# tiny_fox_predatronics.net
KiCad netlist of a schematic drawn in EAGLE
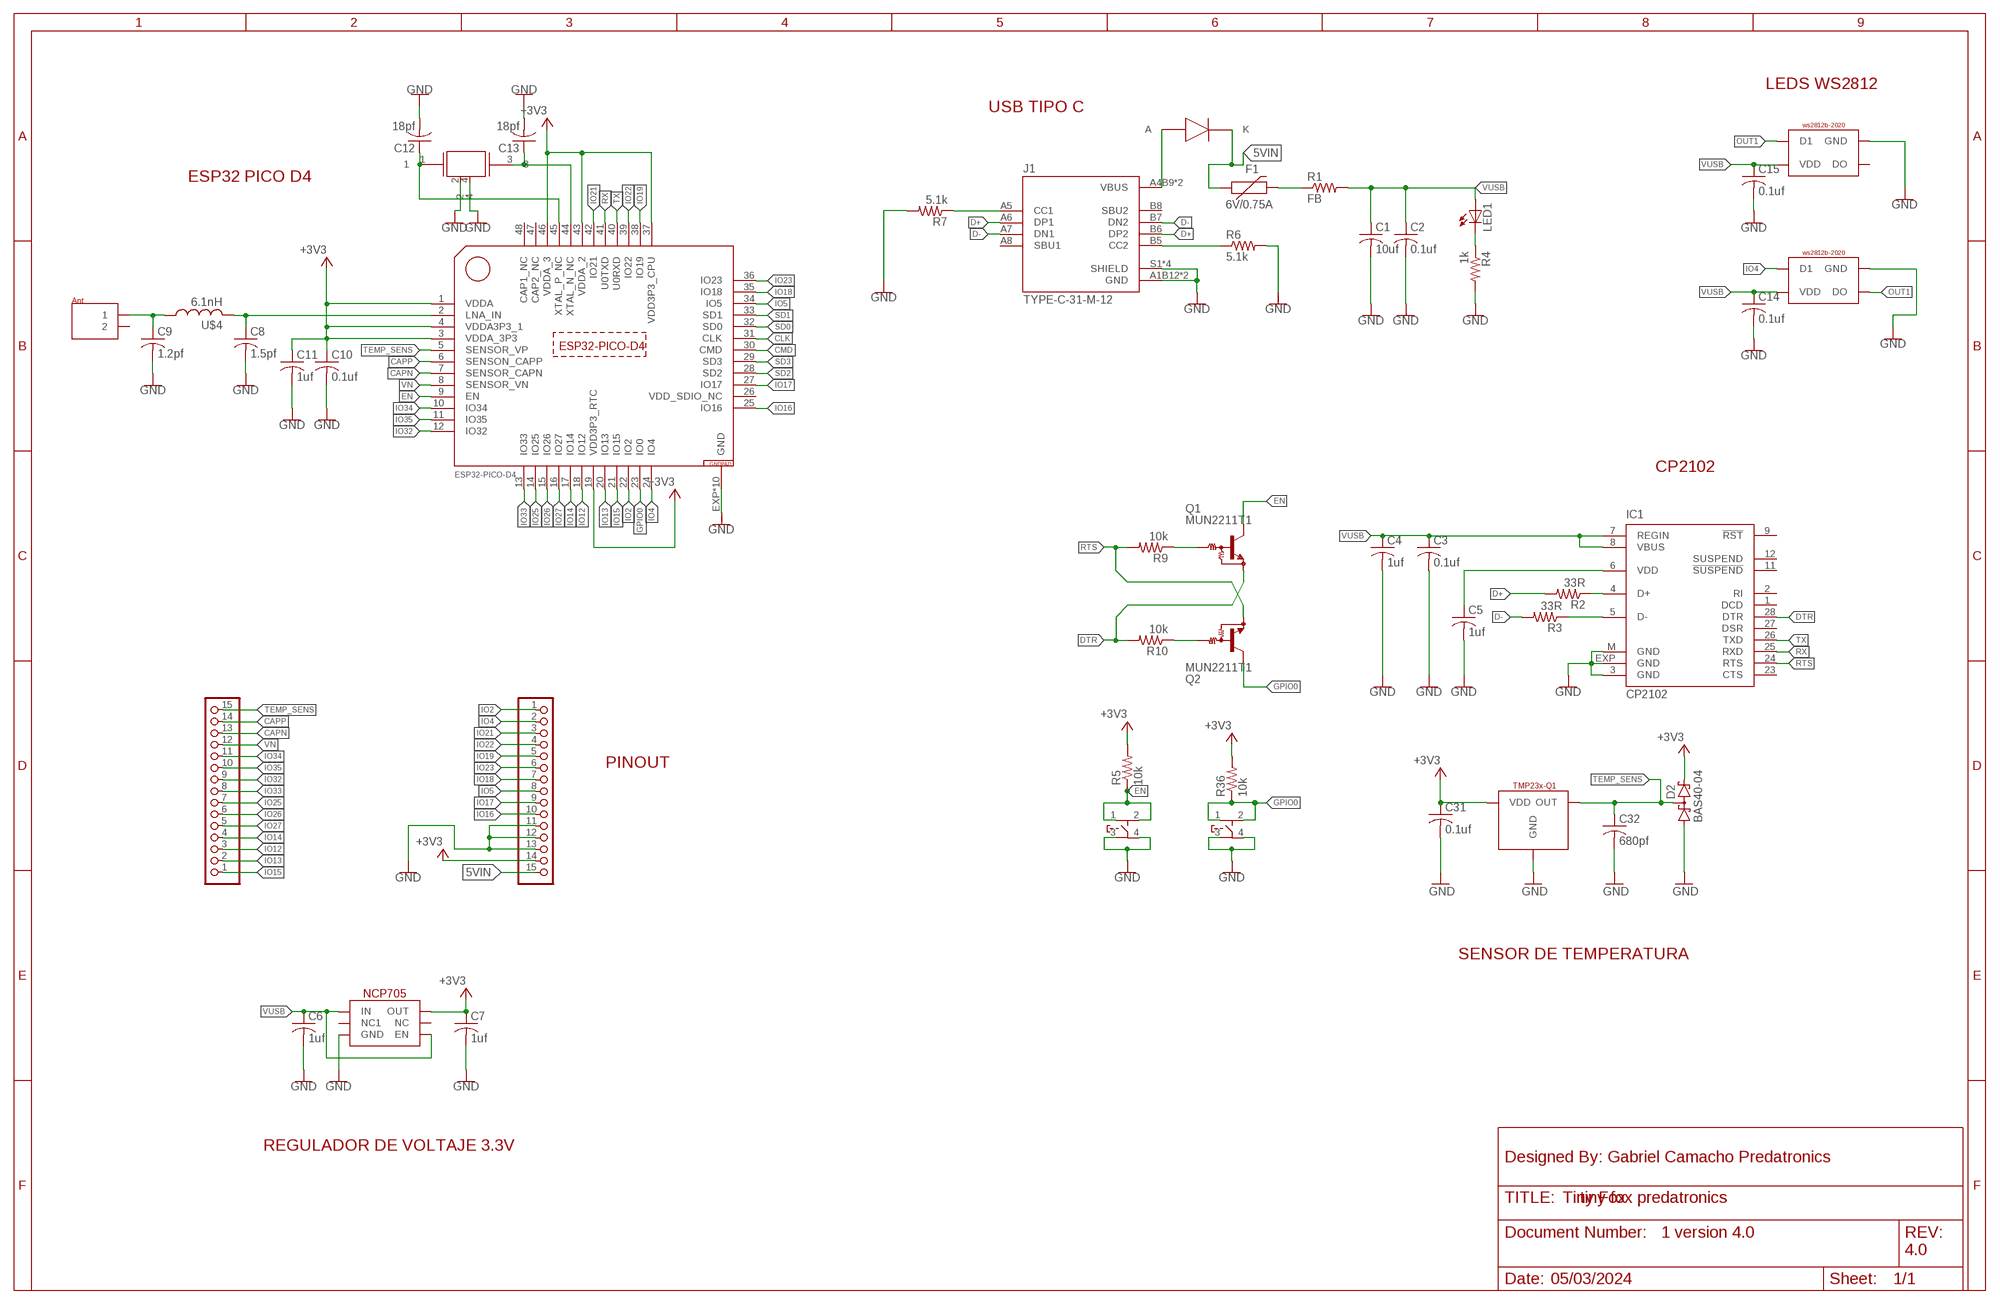
[diagram p0: schematic, sheet 1]

(export (version "E")
  (design (tool "Eeschema 10.0.6"))
  (components
    (comp (ref "C1")
      (value "10uf")
      (footprint "eagle-import:C0805")
      (libsource (lib "eagle-import") (part "C-USC0805"))
    )
    (comp (ref "C2")
      (value "0.1uf")
      (footprint "eagle-import:C0603")
      (libsource (lib "eagle-import") (part "C-USC0603"))
    )
    (comp (ref "C3")
      (value "0.1uf")
      (footprint "eagle-import:C0603")
      (libsource (lib "eagle-import") (part "C-USC0603"))
    )
    (comp (ref "C4")
      (value "1uf")
      (footprint "eagle-import:C0603")
      (libsource (lib "eagle-import") (part "C-USC0603"))
    )
    (comp (ref "C5")
      (value "1uf")
      (footprint "eagle-import:C0603")
      (libsource (lib "eagle-import") (part "C-USC0603"))
    )
    (comp (ref "C6")
      (value "1uf")
      (footprint "eagle-import:C0603")
      (libsource (lib "eagle-import") (part "C-USC0603"))
    )
    (comp (ref "C7")
      (value "1uf")
      (footprint "eagle-import:C0603")
      (libsource (lib "eagle-import") (part "C-USC0603"))
    )
    (comp (ref "C8")
      (value "1.5pf")
      (footprint "eagle-import:C0402")
      (libsource (lib "eagle-import") (part "C-USC0402"))
    )
    (comp (ref "C9")
      (value "1.2pf")
      (footprint "eagle-import:C0402")
      (libsource (lib "eagle-import") (part "C-USC0402"))
    )
    (comp (ref "C10")
      (value "0.1uf")
      (footprint "eagle-import:C0603")
      (libsource (lib "eagle-import") (part "C-USC0603"))
    )
    (comp (ref "C11")
      (value "1uf")
      (footprint "eagle-import:C0603")
      (libsource (lib "eagle-import") (part "C-USC0603"))
    )
    (comp (ref "C12")
      (value "18pf")
      (footprint "eagle-import:C0603")
      (libsource (lib "eagle-import") (part "C-USC0603"))
    )
    (comp (ref "C13")
      (value "18pf")
      (footprint "eagle-import:C0603")
      (libsource (lib "eagle-import") (part "C-USC0603"))
    )
    (comp (ref "C14")
      (value "0.1uf")
      (footprint "eagle-import:C0603")
      (libsource (lib "eagle-import") (part "C-USC0603"))
    )
    (comp (ref "C15")
      (value "0.1uf")
      (footprint "eagle-import:C0603")
      (libsource (lib "eagle-import") (part "C-USC0603"))
    )
    (comp (ref "C31")
      (value "0.1uf")
      (footprint "eagle-import:C0603")
      (libsource (lib "eagle-import") (part "C-USC0603"))
    )
    (comp (ref "C32")
      (value "680pf")
      (footprint "eagle-import:C0603")
      (libsource (lib "eagle-import") (part "C-USC0603"))
    )
    (comp (ref "D2")
      (value "BAS40-04")
      (footprint "eagle-import:SOT23")
      (libsource (lib "eagle-import") (part "BAS40-04"))
    )
    (comp (ref "F1")
      (value "6V/0.75A")
      (footprint "eagle-import:1206")
      (libsource (lib "eagle-import") (part "PPTC_THREE-QUARTER-AMP"))
    )
    (comp (ref "IC1")
      (value "CP2102")
      (footprint "eagle-import:MLP28")
      (fields (field (name "MF") "FARNELL") (field (name "MPN") "CP2102-GM"))
      (libsource (lib "eagle-import") (part "CP2102"))
    )
    (comp (ref "J1")
      (value "TYPE-C-31-M-12")
      (footprint "eagle-import:HRO_TYPE-C-31-M-12")
      (fields (field (name "MF") "HRO Electronics Co., Ltd."))
      (libsource (lib "eagle-import") (part "TYPE-C-31-M-12"))
    )
    (comp (ref "JP1")
      (value "PINHD-1X15")
      (footprint "eagle-import:1X15")
      (libsource (lib "eagle-import") (part "PINHD-1X15"))
    )
    (comp (ref "JP2")
      (value "PINHD-1X15")
      (footprint "eagle-import:1X15")
      (libsource (lib "eagle-import") (part "PINHD-1X15"))
    )
    (comp (ref "LED1")
      (value "LEDCHIPLED_0603")
      (footprint "eagle-import:CHIPLED_0603")
      (libsource (lib "eagle-import") (part "LEDCHIPLED_0603"))
    )
    (comp (ref "Q1")
      (value "MUN2211T1")
      (footprint "eagle-import:SC59-BEC")
      (libsource (lib "eagle-import") (part "MUN2211T1"))
    )
    (comp (ref "Q2")
      (value "MUN2211T1")
      (footprint "eagle-import:SC59-BEC")
      (libsource (lib "eagle-import") (part "MUN2211T1"))
    )
    (comp (ref "R1")
      (value "FB")
      (footprint "eagle-import:R0805")
      (libsource (lib "eagle-import") (part "audio amplifier example_970892_R-US_R0805"))
    )
    (comp (ref "R2")
      (value "33R")
      (footprint "eagle-import:R0603")
      (libsource (lib "eagle-import") (part "resistor_348_R-US_R0603"))
    )
    (comp (ref "R3")
      (value "33R")
      (footprint "eagle-import:R0603")
      (libsource (lib "eagle-import") (part "resistor_348_R-US_R0603"))
    )
    (comp (ref "R4")
      (value "1k")
      (footprint "eagle-import:R0603")
      (libsource (lib "eagle-import") (part "resistor_348_R-US_R0603"))
    )
    (comp (ref "R5")
      (value "10k")
      (footprint "eagle-import:R0603")
      (libsource (lib "eagle-import") (part "R-US_R0603"))
    )
    (comp (ref "R6")
      (value "5.1k")
      (footprint "eagle-import:R0402")
      (libsource (lib "eagle-import") (part "rcl_334_R-US_R0402"))
    )
    (comp (ref "R7")
      (value "5.1k")
      (footprint "eagle-import:R0402")
      (libsource (lib "eagle-import") (part "rcl_334_R-US_R0402"))
    )
    (comp (ref "R9")
      (value "10k")
      (footprint "eagle-import:R0603")
      (libsource (lib "eagle-import") (part "resistor_348_R-US_R0603"))
    )
    (comp (ref "R10")
      (value "10k")
      (footprint "eagle-import:R0603")
      (libsource (lib "eagle-import") (part "resistor_348_R-US_R0603"))
    )
    (comp (ref "R36")
      (value "10k")
      (footprint "eagle-import:R0603")
      (libsource (lib "eagle-import") (part "R-US_R0603"))
    )
    (comp (ref "U$1")
      (value "ESP32-PICO-D4")
      (footprint "eagle-import:QFN48")
      (libsource (lib "eagle-import") (part "ESP32-PICO-D4"))
    )
    (comp (ref "U$2")
      (value "WS2812B-2020")
      (footprint "eagle-import:2020")
      (libsource (lib "eagle-import") (part "WS2812B-2020"))
    )
    (comp (ref "U$3")
      (value "NCP705")
      (footprint "eagle-import:WDFN6")
      (libsource (lib "eagle-import") (part "NCP705"))
    )
    (comp (ref "U$4")
      (value "6.1nH")
      (footprint "eagle-import:RESC0402_M")
      (libsource (lib "eagle-import") (part "INDUCTOR_0402_M"))
    )
    (comp (ref "U$5")
      (value "CHIP-ANTHENA")
      (footprint "eagle-import:ANTHENFOOT")
      (libsource (lib "eagle-import") (part "CHIP-ANTHENA"))
    )
    (comp (ref "U$6")
      (value "ECX-32")
      (footprint "eagle-import:EXC-32")
      (libsource (lib "eagle-import") (part "ECX-32"))
    )
    (comp (ref "U$7")
      (value "WS2812B-2020")
      (footprint "eagle-import:2020")
      (libsource (lib "eagle-import") (part "WS2812B-2020"))
    )
    (comp (ref "U$10")
      (value "RB160MM-50TF")
      (footprint "eagle-import:SOD-123FL")
      (libsource (lib "eagle-import") (part "RB160MM-50TF"))
    )
    (comp (ref "U$21")
      (value "TMP23X-Q1")
      (footprint "eagle-import:SOT-23")
      (libsource (lib "eagle-import") (part "TMP23X-Q1"))
    )
    (comp (ref "U$22")
      (value "XUNPU")
      (footprint "eagle-import:TS-1089S")
      (libsource (lib "eagle-import") (part "XUNPU"))
    )
    (comp (ref "U$23")
      (value "XUNPU")
      (footprint "eagle-import:TS-1089S")
      (libsource (lib "eagle-import") (part "XUNPU"))
    )
  )
  (nets
    (net (code "1") (name "+3V3") (class "Default")
      (node (ref "C10") (pin "1") (pinfunction "1_1") (pintype "passive"))
      (node (ref "C11") (pin "1") (pinfunction "1_1") (pintype "passive"))
      (node (ref "C31") (pin "1") (pinfunction "1_1") (pintype "passive"))
      (node (ref "C7") (pin "1") (pinfunction "1_1") (pintype "passive"))
      (node (ref "D2") (pin "2") (pinfunction "C2_2") (pintype "passive"))
      (node (ref "JP2") (pin "14") (pinfunction "14_14") (pintype "passive"))
      (node (ref "R36") (pin "2") (pinfunction "2_2") (pintype "passive"))
      (node (ref "R5") (pin "2") (pinfunction "2_2") (pintype "passive"))
      (node (ref "U$1") (pin "1") (pinfunction "VDDA_1") (pintype "power_in"))
      (node (ref "U$1") (pin "19") (pinfunction "VDD3P3_RTC_19") (pintype "power_in"))
      (node (ref "U$1") (pin "3") (pinfunction "VDDA_3P3_3") (pintype "power_in"))
      (node (ref "U$1") (pin "37") (pinfunction "VDD3P3_CPU_37") (pintype "power_in"))
      (node (ref "U$1") (pin "4") (pinfunction "VDDA3P3_1_4") (pintype "power_in"))
      (node (ref "U$1") (pin "43") (pinfunction "VDDA_2_43") (pintype "power_in"))
      (node (ref "U$1") (pin "46") (pinfunction "VDDA_3_46") (pintype "power_in"))
      (node (ref "U$21") (pin "VDD") (pinfunction "VDD_VDD") (pintype "bidirectional"))
      (node (ref "U$3") (pin "OUT") (pinfunction "OUT_OUT") (pintype "bidirectional"))
    )
    (net (code "2") (name "/VDD_SDIO_NC") (class "Default")
      (node (ref "U$1") (pin "26") (pinfunction "VDD_SDIO_NC_26") (pintype "power_in"))
    )
    (net (code "3") (name "5VIN") (class "Default")
      (node (ref "F1") (pin "1") (pinfunction "1_1") (pintype "bidirectional"))
      (node (ref "JP2") (pin "15") (pinfunction "15_15") (pintype "passive"))
      (node (ref "U$10") (pin "K") (pinfunction "K_K") (pintype "bidirectional"))
    )
    (net (code "4") (name "CAPN") (class "Default")
      (node (ref "JP1") (pin "13") (pinfunction "13_13") (pintype "passive"))
      (node (ref "U$1") (pin "7") (pinfunction "SENSOR_CAPN_7") (pintype "input"))
    )
    (net (code "5") (name "CAPP") (class "Default")
      (node (ref "JP1") (pin "14") (pinfunction "14_14") (pintype "passive"))
      (node (ref "U$1") (pin "6") (pinfunction "SENSON_CAPP_6") (pintype "input"))
    )
    (net (code "6") (name "CLK") (class "Default")
      (node (ref "U$1") (pin "31") (pinfunction "CLK_31") (pintype "bidirectional"))
    )
    (net (code "7") (name "CMD") (class "Default")
      (node (ref "U$1") (pin "30") (pinfunction "CMD_30") (pintype "bidirectional"))
    )
    (net (code "8") (name "D+") (class "Default")
      (node (ref "J1") (pin "A6") (pinfunction "DP1_A6") (pintype "bidirectional"))
      (node (ref "J1") (pin "B6") (pinfunction "DP2_B6") (pintype "bidirectional"))
      (node (ref "R2") (pin "2") (pinfunction "2_2") (pintype "passive"))
    )
    (net (code "9") (name "D-") (class "Default")
      (node (ref "J1") (pin "A7") (pinfunction "DN1_A7") (pintype "bidirectional"))
      (node (ref "J1") (pin "B7") (pinfunction "DN2_B7") (pintype "bidirectional"))
      (node (ref "R3") (pin "2") (pinfunction "2_2") (pintype "passive"))
    )
    (net (code "10") (name "DTR") (class "Default")
      (node (ref "IC1") (pin "28") (pinfunction "DTR_28") (pintype "output"))
      (node (ref "Q1") (pin "E") (pinfunction "E_E") (pintype "passive"))
      (node (ref "R10") (pin "2") (pinfunction "2_2") (pintype "passive"))
    )
    (net (code "11") (name "EN") (class "Default")
      (node (ref "Q1") (pin "C") (pinfunction "C_C") (pintype "passive"))
      (node (ref "R5") (pin "1") (pinfunction "1_1") (pintype "passive"))
      (node (ref "U$1") (pin "9") (pinfunction "EN_9") (pintype "input"))
      (node (ref "U$22") (pin "1") (pinfunction "1_1") (pintype "bidirectional"))
      (node (ref "U$22") (pin "2") (pinfunction "2_2") (pintype "bidirectional"))
    )
    (net (code "12") (name "GND") (class "Default")
      (node (ref "C1") (pin "2") (pinfunction "2_2") (pintype "passive"))
      (node (ref "C10") (pin "2") (pinfunction "2_2") (pintype "passive"))
      (node (ref "C11") (pin "2") (pinfunction "2_2") (pintype "passive"))
      (node (ref "C12") (pin "2") (pinfunction "2_2") (pintype "passive"))
      (node (ref "C13") (pin "2") (pinfunction "2_2") (pintype "passive"))
      (node (ref "C14") (pin "2") (pinfunction "2_2") (pintype "passive"))
      (node (ref "C15") (pin "2") (pinfunction "2_2") (pintype "passive"))
      (node (ref "C2") (pin "2") (pinfunction "2_2") (pintype "passive"))
      (node (ref "C3") (pin "2") (pinfunction "2_2") (pintype "passive"))
      (node (ref "C31") (pin "2") (pinfunction "2_2") (pintype "passive"))
      (node (ref "C32") (pin "2") (pinfunction "2_2") (pintype "passive"))
      (node (ref "C4") (pin "2") (pinfunction "2_2") (pintype "passive"))
      (node (ref "C5") (pin "2") (pinfunction "2_2") (pintype "passive"))
      (node (ref "C6") (pin "2") (pinfunction "2_2") (pintype "passive"))
      (node (ref "C7") (pin "2") (pinfunction "2_2") (pintype "passive"))
      (node (ref "C8") (pin "2") (pinfunction "2_2") (pintype "passive"))
      (node (ref "C9") (pin "2") (pinfunction "2_2") (pintype "passive"))
      (node (ref "D2") (pin "1") (pinfunction "A1_1") (pintype "passive"))
      (node (ref "IC1") (pin "3") (pinfunction "GND_3") (pintype "power_in"))
      (node (ref "IC1") (pin "EXP") (pinfunction "GND_EXP") (pintype "power_in"))
      (node (ref "IC1") (pin "M") (pinfunction "GND_M") (pintype "power_in"))
      (node (ref "J1") (pin "A1B12") (pinfunction "GND_A1B12") (pintype "power_in"))
      (node (ref "J1") (pin "B1A12") (pinfunction "GND_B1A12") (pintype "power_in"))
      (node (ref "J1") (pin "S1") (pinfunction "SHIELD_S1") (pintype "passive"))
      (node (ref "J1") (pin "S2") (pinfunction "SHIELD_S2") (pintype "passive"))
      (node (ref "J1") (pin "S3") (pinfunction "SHIELD_S3") (pintype "passive"))
      (node (ref "J1") (pin "S4") (pinfunction "SHIELD_S4") (pintype "passive"))
      (node (ref "JP2") (pin "11") (pinfunction "11_11") (pintype "passive"))
      (node (ref "JP2") (pin "12") (pinfunction "12_12") (pintype "passive"))
      (node (ref "JP2") (pin "13") (pinfunction "13_13") (pintype "passive"))
      (node (ref "R4") (pin "2") (pinfunction "2_2") (pintype "passive"))
      (node (ref "R6") (pin "2") (pinfunction "2_2") (pintype "passive"))
      (node (ref "R7") (pin "2") (pinfunction "2_2") (pintype "passive"))
      (node (ref "U$1") (pin "EXP") (pinfunction "GND_EXP") (pintype "power_in"))
      (node (ref "U$1") (pin "P$1") (pinfunction "GND_P$1") (pintype "power_in"))
      (node (ref "U$1") (pin "P$2") (pinfunction "GND_P$2") (pintype "power_in"))
      (node (ref "U$1") (pin "P$3") (pinfunction "GND_P$3") (pintype "power_in"))
      (node (ref "U$1") (pin "P$4") (pinfunction "GND_P$4") (pintype "power_in"))
      (node (ref "U$1") (pin "P$5") (pinfunction "GND_P$5") (pintype "power_in"))
      (node (ref "U$1") (pin "P$6") (pinfunction "GND_P$6") (pintype "power_in"))
      (node (ref "U$1") (pin "P$7") (pinfunction "GND_P$7") (pintype "power_in"))
      (node (ref "U$1") (pin "P$8") (pinfunction "GND_P$8") (pintype "power_in"))
      (node (ref "U$1") (pin "P$9") (pinfunction "GND_P$9") (pintype "power_in"))
      (node (ref "U$2") (pin "GND") (pinfunction "GND_GND") (pintype "bidirectional"))
      (node (ref "U$21") (pin "GND") (pinfunction "GND_GND") (pintype "bidirectional"))
      (node (ref "U$22") (pin "3") (pinfunction "3_3") (pintype "bidirectional"))
      (node (ref "U$22") (pin "4") (pinfunction "4_4") (pintype "bidirectional"))
      (node (ref "U$23") (pin "3") (pinfunction "3_3") (pintype "bidirectional"))
      (node (ref "U$23") (pin "4") (pinfunction "4_4") (pintype "bidirectional"))
      (node (ref "U$3") (pin "GND") (pinfunction "GND_GND") (pintype "bidirectional"))
      (node (ref "U$3") (pin "P$7") (pinfunction "GND_P$7") (pintype "bidirectional"))
      (node (ref "U$3") (pin "P$8") (pinfunction "GND_P$8") (pintype "bidirectional"))
      (node (ref "U$6") (pin "2") (pinfunction "2_2") (pintype "bidirectional"))
      (node (ref "U$6") (pin "4") (pinfunction "4_4") (pintype "bidirectional"))
      (node (ref "U$7") (pin "GND") (pinfunction "GND_GND") (pintype "bidirectional"))
    )
    (net (code "13") (name "GPIO0") (class "Default")
      (node (ref "Q2") (pin "C") (pinfunction "C_C") (pintype "passive"))
      (node (ref "R36") (pin "1") (pinfunction "1_1") (pintype "passive"))
      (node (ref "U$1") (pin "23") (pinfunction "IO0_23") (pintype "bidirectional"))
      (node (ref "U$23") (pin "1") (pinfunction "1_1") (pintype "bidirectional"))
      (node (ref "U$23") (pin "2") (pinfunction "2_2") (pintype "bidirectional"))
    )
    (net (code "14") (name "IO2") (class "Default")
      (node (ref "JP2") (pin "1") (pinfunction "1_1") (pintype "passive"))
      (node (ref "U$1") (pin "22") (pinfunction "IO2_22") (pintype "bidirectional"))
    )
    (net (code "15") (name "IO4") (class "Default")
      (node (ref "JP2") (pin "2") (pinfunction "2_2") (pintype "passive"))
      (node (ref "U$1") (pin "24") (pinfunction "IO4_24") (pintype "bidirectional"))
      (node (ref "U$2") (pin "D1") (pinfunction "D1_D1") (pintype "bidirectional"))
    )
    (net (code "16") (name "IO5") (class "Default")
      (node (ref "JP2") (pin "8") (pinfunction "8_8") (pintype "passive"))
      (node (ref "U$1") (pin "34") (pinfunction "IO5_34") (pintype "bidirectional"))
    )
    (net (code "17") (name "IO12") (class "Default")
      (node (ref "JP1") (pin "3") (pinfunction "3_3") (pintype "passive"))
      (node (ref "U$1") (pin "18") (pinfunction "IO12_18") (pintype "bidirectional"))
    )
    (net (code "18") (name "IO13") (class "Default")
      (node (ref "JP1") (pin "2") (pinfunction "2_2") (pintype "passive"))
      (node (ref "U$1") (pin "20") (pinfunction "IO13_20") (pintype "bidirectional"))
    )
    (net (code "19") (name "IO14") (class "Default")
      (node (ref "JP1") (pin "4") (pinfunction "4_4") (pintype "passive"))
      (node (ref "U$1") (pin "17") (pinfunction "IO14_17") (pintype "bidirectional"))
    )
    (net (code "20") (name "IO15") (class "Default")
      (node (ref "JP1") (pin "1") (pinfunction "1_1") (pintype "passive"))
      (node (ref "U$1") (pin "21") (pinfunction "IO15_21") (pintype "bidirectional"))
    )
    (net (code "21") (name "IO16") (class "Default")
      (node (ref "JP2") (pin "10") (pinfunction "10_10") (pintype "passive"))
      (node (ref "U$1") (pin "25") (pinfunction "IO16_25") (pintype "bidirectional"))
    )
    (net (code "22") (name "IO17") (class "Default")
      (node (ref "JP2") (pin "9") (pinfunction "9_9") (pintype "passive"))
      (node (ref "U$1") (pin "27") (pinfunction "IO17_27") (pintype "bidirectional"))
    )
    (net (code "23") (name "IO18") (class "Default")
      (node (ref "JP2") (pin "7") (pinfunction "7_7") (pintype "passive"))
      (node (ref "U$1") (pin "35") (pinfunction "IO18_35") (pintype "bidirectional"))
    )
    (net (code "24") (name "IO19") (class "Default")
      (node (ref "JP2") (pin "5") (pinfunction "5_5") (pintype "passive"))
      (node (ref "U$1") (pin "38") (pinfunction "IO19_38") (pintype "bidirectional"))
    )
    (net (code "25") (name "IO21") (class "Default")
      (node (ref "JP2") (pin "3") (pinfunction "3_3") (pintype "passive"))
      (node (ref "U$1") (pin "42") (pinfunction "IO21_42") (pintype "bidirectional"))
    )
    (net (code "26") (name "IO22") (class "Default")
      (node (ref "JP2") (pin "4") (pinfunction "4_4") (pintype "passive"))
      (node (ref "U$1") (pin "39") (pinfunction "IO22_39") (pintype "bidirectional"))
    )
    (net (code "27") (name "IO23") (class "Default")
      (node (ref "JP2") (pin "6") (pinfunction "6_6") (pintype "passive"))
      (node (ref "U$1") (pin "36") (pinfunction "IO23_36") (pintype "bidirectional"))
    )
    (net (code "28") (name "IO25") (class "Default")
      (node (ref "JP1") (pin "7") (pinfunction "7_7") (pintype "passive"))
      (node (ref "U$1") (pin "14") (pinfunction "IO25_14") (pintype "bidirectional"))
    )
    (net (code "29") (name "IO26") (class "Default")
      (node (ref "JP1") (pin "6") (pinfunction "6_6") (pintype "passive"))
      (node (ref "U$1") (pin "15") (pinfunction "IO26_15") (pintype "bidirectional"))
    )
    (net (code "30") (name "IO27") (class "Default")
      (node (ref "JP1") (pin "5") (pinfunction "5_5") (pintype "passive"))
      (node (ref "U$1") (pin "16") (pinfunction "IO27_16") (pintype "bidirectional"))
    )
    (net (code "31") (name "IO32") (class "Default")
      (node (ref "JP1") (pin "9") (pinfunction "9_9") (pintype "passive"))
      (node (ref "U$1") (pin "12") (pinfunction "IO32_12") (pintype "bidirectional"))
    )
    (net (code "32") (name "IO33") (class "Default")
      (node (ref "JP1") (pin "8") (pinfunction "8_8") (pintype "passive"))
      (node (ref "U$1") (pin "13") (pinfunction "IO33_13") (pintype "bidirectional"))
    )
    (net (code "33") (name "IO34") (class "Default")
      (node (ref "JP1") (pin "11") (pinfunction "11_11") (pintype "passive"))
      (node (ref "U$1") (pin "10") (pinfunction "IO34_10") (pintype "bidirectional"))
    )
    (net (code "34") (name "IO35") (class "Default")
      (node (ref "JP1") (pin "10") (pinfunction "10_10") (pintype "passive"))
      (node (ref "U$1") (pin "11") (pinfunction "IO35_11") (pintype "bidirectional"))
    )
    (net (code "35") (name "Net-(C9-Pad1)") (class "Default")
      (node (ref "C9") (pin "1") (pinfunction "1_1") (pintype "passive"))
      (node (ref "U$4") (pin "1") (pinfunction "1_1") (pintype "passive"))
      (node (ref "U$5") (pin "1") (pinfunction "1_1") (pintype "bidirectional"))
    )
    (net (code "36") (name "Net-(F1-Pad2)") (class "Default")
      (node (ref "F1") (pin "2") (pinfunction "2_2") (pintype "bidirectional"))
      (node (ref "R1") (pin "1") (pinfunction "1_1") (pintype "passive"))
    )
    (net (code "37") (name "Net-(IC1-D+)") (class "Default")
      (node (ref "IC1") (pin "4") (pinfunction "D+_4") (pintype "bidirectional"))
      (node (ref "R2") (pin "1") (pinfunction "1_1") (pintype "passive"))
    )
    (net (code "38") (name "Net-(IC1-D-)") (class "Default")
      (node (ref "IC1") (pin "5") (pinfunction "D-_5") (pintype "bidirectional"))
      (node (ref "R3") (pin "1") (pinfunction "1_1") (pintype "passive"))
    )
    (net (code "39") (name "Net-(IC1-VDD)") (class "Default")
      (node (ref "C5") (pin "1") (pinfunction "1_1") (pintype "passive"))
      (node (ref "IC1") (pin "6") (pinfunction "VDD_6") (pintype "power_in"))
    )
    (net (code "40") (name "Net-(J1-CC1)") (class "Default")
      (node (ref "J1") (pin "A5") (pinfunction "CC1_A5") (pintype "bidirectional"))
      (node (ref "R7") (pin "1") (pinfunction "1_1") (pintype "passive"))
    )
    (net (code "41") (name "Net-(J1-CC2)") (class "Default")
      (node (ref "J1") (pin "B5") (pinfunction "CC2_B5") (pintype "bidirectional"))
      (node (ref "R6") (pin "1") (pinfunction "1_1") (pintype "passive"))
    )
    (net (code "42") (name "Net-(J1-VBUS-PadA4B9)") (class "Default")
      (node (ref "J1") (pin "A4B9") (pinfunction "VBUS_A4B9") (pintype "power_in"))
      (node (ref "J1") (pin "B4A9") (pinfunction "VBUS_B4A9") (pintype "power_in"))
      (node (ref "U$10") (pin "A") (pinfunction "A_A") (pintype "bidirectional"))
    )
    (net (code "43") (name "Net-(LED1-PadC)") (class "Default")
      (node (ref "LED1") (pin "C") (pinfunction "C_C") (pintype "passive"))
      (node (ref "R4") (pin "1") (pinfunction "1_1") (pintype "passive"))
    )
    (net (code "44") (name "Net-(Q1-PadB)") (class "Default")
      (node (ref "Q1") (pin "B") (pinfunction "B_B") (pintype "passive"))
      (node (ref "R9") (pin "1") (pinfunction "1_1") (pintype "passive"))
    )
    (net (code "45") (name "Net-(Q2-PadB)") (class "Default")
      (node (ref "Q2") (pin "B") (pinfunction "B_B") (pintype "passive"))
      (node (ref "R10") (pin "1") (pinfunction "1_1") (pintype "passive"))
    )
    (net (code "46") (name "Net-(U$1-LNA_IN)") (class "Default")
      (node (ref "C8") (pin "1") (pinfunction "1_1") (pintype "passive"))
      (node (ref "U$1") (pin "2") (pinfunction "LNA_IN_2") (pintype "bidirectional"))
      (node (ref "U$4") (pin "2") (pinfunction "2_2") (pintype "passive"))
    )
    (net (code "47") (name "Net-(U$1-XTAL_N_NC)") (class "Default")
      (node (ref "C13") (pin "1") (pinfunction "1_1") (pintype "passive"))
      (node (ref "U$1") (pin "44") (pinfunction "XTAL_N_NC_44") (pintype "bidirectional"))
      (node (ref "U$6") (pin "3") (pinfunction "3_3") (pintype "bidirectional"))
    )
    (net (code "48") (name "Net-(U$1-XTAL_P_NC)") (class "Default")
      (node (ref "C12") (pin "1") (pinfunction "1_1") (pintype "passive"))
      (node (ref "U$1") (pin "45") (pinfunction "XTAL_P_NC_45") (pintype "bidirectional"))
      (node (ref "U$6") (pin "1") (pinfunction "1_1") (pintype "bidirectional"))
    )
    (net (code "49") (name "OUT1") (class "Default")
      (node (ref "U$2") (pin "DO") (pinfunction "DO_DO") (pintype "bidirectional"))
      (node (ref "U$7") (pin "D1") (pinfunction "D1_D1") (pintype "bidirectional"))
    )
    (net (code "50") (name "RTS") (class "Default")
      (node (ref "IC1") (pin "24") (pinfunction "RTS_24") (pintype "output"))
      (node (ref "Q2") (pin "E") (pinfunction "E_E") (pintype "passive"))
      (node (ref "R9") (pin "2") (pinfunction "2_2") (pintype "passive"))
    )
    (net (code "51") (name "RX") (class "Default")
      (node (ref "IC1") (pin "25") (pinfunction "RXD_25") (pintype "input"))
      (node (ref "U$1") (pin "41") (pinfunction "U0TXD_41") (pintype "bidirectional"))
    )
    (net (code "52") (name "SD0") (class "Default")
      (node (ref "U$1") (pin "32") (pinfunction "SD0_32") (pintype "bidirectional"))
    )
    (net (code "53") (name "SD1") (class "Default")
      (node (ref "U$1") (pin "33") (pinfunction "SD1_33") (pintype "bidirectional"))
    )
    (net (code "54") (name "SD2") (class "Default")
      (node (ref "U$1") (pin "28") (pinfunction "SD2_28") (pintype "bidirectional"))
    )
    (net (code "55") (name "SD3") (class "Default")
      (node (ref "U$1") (pin "29") (pinfunction "SD3_29") (pintype "bidirectional"))
    )
    (net (code "56") (name "TEMP_SENS") (class "Default")
      (node (ref "C32") (pin "1") (pinfunction "1_1") (pintype "passive"))
      (node (ref "D2") (pin "3") (pinfunction "C1A2_3") (pintype "passive"))
      (node (ref "JP1") (pin "15") (pinfunction "15_15") (pintype "passive"))
      (node (ref "U$1") (pin "5") (pinfunction "SENSOR_VP_5") (pintype "input"))
      (node (ref "U$21") (pin "VOUT") (pinfunction "OUT_VOUT") (pintype "bidirectional"))
    )
    (net (code "57") (name "TX") (class "Default")
      (node (ref "IC1") (pin "26") (pinfunction "TXD_26") (pintype "output"))
      (node (ref "U$1") (pin "40") (pinfunction "U0RXD_40") (pintype "bidirectional"))
    )
    (net (code "58") (name "VN") (class "Default")
      (node (ref "JP1") (pin "12") (pinfunction "12_12") (pintype "passive"))
      (node (ref "U$1") (pin "8") (pinfunction "SENSOR_VN_8") (pintype "input"))
    )
    (net (code "59") (name "VUSB") (class "Default")
      (node (ref "C1") (pin "1") (pinfunction "1_1") (pintype "passive"))
      (node (ref "C14") (pin "1") (pinfunction "1_1") (pintype "passive"))
      (node (ref "C15") (pin "1") (pinfunction "1_1") (pintype "passive"))
      (node (ref "C2") (pin "1") (pinfunction "1_1") (pintype "passive"))
      (node (ref "C3") (pin "1") (pinfunction "1_1") (pintype "passive"))
      (node (ref "C4") (pin "1") (pinfunction "1_1") (pintype "passive"))
      (node (ref "C6") (pin "1") (pinfunction "1_1") (pintype "passive"))
      (node (ref "IC1") (pin "7") (pinfunction "REGIN_7") (pintype "passive"))
      (node (ref "IC1") (pin "8") (pinfunction "VBUS_8") (pintype "input"))
      (node (ref "LED1") (pin "A") (pinfunction "A_A") (pintype "passive"))
      (node (ref "R1") (pin "2") (pinfunction "2_2") (pintype "passive"))
      (node (ref "U$2") (pin "VDD") (pinfunction "VDD_VDD") (pintype "bidirectional"))
      (node (ref "U$3") (pin "EN") (pinfunction "EN_EN") (pintype "bidirectional"))
      (node (ref "U$3") (pin "IN") (pinfunction "IN_IN") (pintype "bidirectional"))
      (node (ref "U$7") (pin "VDD") (pinfunction "VDD_VDD") (pintype "bidirectional"))
    )
    (net (code "60") (name "unconnected-(IC1-CTS-Pad23)") (class "Default")
      (node (ref "IC1") (pin "23") (pinfunction "CTS_23") (pintype "input"))
    )
    (net (code "61") (name "unconnected-(IC1-DCD-Pad1)") (class "Default")
      (node (ref "IC1") (pin "1") (pinfunction "DCD_1") (pintype "input"))
    )
    (net (code "62") (name "unconnected-(IC1-DSR-Pad27)") (class "Default")
      (node (ref "IC1") (pin "27") (pinfunction "DSR_27") (pintype "input"))
    )
    (net (code "63") (name "unconnected-(IC1-RI-Pad2)") (class "Default")
      (node (ref "IC1") (pin "2") (pinfunction "RI_2") (pintype "input"))
    )
    (net (code "64") (name "unconnected-(IC1-SUSPEND-Pad12)") (class "Default")
      (node (ref "IC1") (pin "12") (pinfunction "SUSPEND_12") (pintype "output"))
    )
    (net (code "65") (name "unconnected-(IC1-~{RST}-Pad9)") (class "Default")
      (node (ref "IC1") (pin "9") (pinfunction "~{RST}_9") (pintype "bidirectional"))
    )
    (net (code "66") (name "unconnected-(IC1-~{SUSPEND}-Pad11)") (class "Default")
      (node (ref "IC1") (pin "11") (pinfunction "~{SUSPEND}_11") (pintype "output"))
    )
    (net (code "67") (name "unconnected-(J1-SBU1-PadA8)") (class "Default")
      (node (ref "J1") (pin "A8") (pinfunction "SBU1_A8") (pintype "bidirectional"))
    )
    (net (code "68") (name "unconnected-(J1-SBU2-PadB8)") (class "Default")
      (node (ref "J1") (pin "B8") (pinfunction "SBU2_B8") (pintype "bidirectional"))
    )
    (net (code "69") (name "unconnected-(U$1-CAP1_NC-Pad48)") (class "Default")
      (node (ref "U$1") (pin "48") (pinfunction "CAP1_NC_48") (pintype "bidirectional"))
    )
    (net (code "70") (name "unconnected-(U$1-CAP2_NC-Pad47)") (class "Default")
      (node (ref "U$1") (pin "47") (pinfunction "CAP2_NC_47") (pintype "bidirectional"))
    )
    (net (code "71") (name "unconnected-(U$3-PadNC)") (class "Default")
      (node (ref "U$3") (pin "NC") (pinfunction "NC_NC") (pintype "bidirectional"))
    )
    (net (code "72") (name "unconnected-(U$3-PadNC1)") (class "Default")
      (node (ref "U$3") (pin "NC1") (pinfunction "NC1_NC1") (pintype "bidirectional"))
    )
    (net (code "73") (name "unconnected-(U$5-Pad2)") (class "Default")
      (node (ref "U$5") (pin "2") (pinfunction "2_2") (pintype "bidirectional"))
    )
    (net (code "74") (name "unconnected-(U$7-PadDO)") (class "Default")
      (node (ref "U$7") (pin "DO") (pinfunction "DO_DO") (pintype "bidirectional"))
    )
  )
)
